# ESFDv1.net
KiCad netlist of a schematic drawn in EAGLE
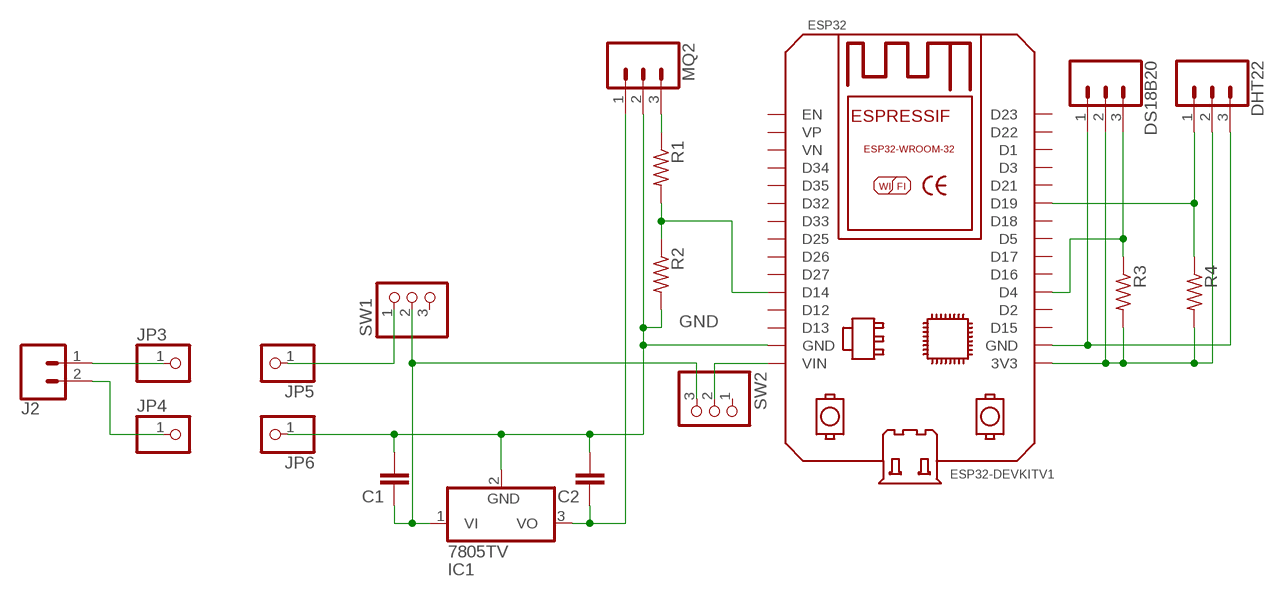
[diagram p0: schematic, sheet 1]

(export (version "E")
  (design (tool "Eeschema 10.0.6"))
  (components
    (comp (ref "C1")
      (value "C5/2.5")
      (footprint "eagle-import:C5B2.5")
      (libsource (lib "eagle-import") (part "C5/2.5"))
    )
    (comp (ref "C2")
      (value "C5/2.5")
      (footprint "eagle-import:C5B2.5")
      (libsource (lib "eagle-import") (part "C5/2.5"))
    )
    (comp (ref "DHT22")
      (value "CONN_03-SCREW-5MM")
      (footprint "eagle-import:SCREWTERMINAL-5MM-3")
      (libsource (lib "eagle-import") (part "CONN_03-SCREW-5MM"))
    )
    (comp (ref "DS18B20")
      (value "CONN_03-SCREW-5MM")
      (footprint "eagle-import:SCREWTERMINAL-5MM-3")
      (libsource (lib "eagle-import") (part "CONN_03-SCREW-5MM"))
    )
    (comp (ref "ESP32")
      (value "ESP32DEVKITV1")
      (footprint "eagle-import:ESP32-DEVKITV1")
      (libsource (lib "eagle-import") (part "ESP32DEVKITV1"))
    )
    (comp (ref "IC1")
      (value "7805TV")
      (footprint "eagle-import:TO220V")
      (libsource (lib "eagle-import") (part "78TV05"))
    )
    (comp (ref "J2")
      (value "CONN_025MM")
      (footprint "eagle-import:SCREWTERMINAL-5MM-2")
      (libsource (lib "eagle-import") (part "CONN_025MM"))
    )
    (comp (ref "JP3")
      (value "PINHD-1X1")
      (footprint "eagle-import:1X01")
      (libsource (lib "eagle-import") (part "PINHD-1X1"))
    )
    (comp (ref "JP4")
      (value "PINHD-1X1")
      (footprint "eagle-import:1X01")
      (libsource (lib "eagle-import") (part "PINHD-1X1"))
    )
    (comp (ref "JP5")
      (value "PINHD-1X1")
      (footprint "eagle-import:1X01")
      (libsource (lib "eagle-import") (part "PINHD-1X1"))
    )
    (comp (ref "JP6")
      (value "PINHD-1X1")
      (footprint "eagle-import:1X01")
      (libsource (lib "eagle-import") (part "PINHD-1X1"))
    )
    (comp (ref "MQ2")
      (value "CONN_03-SCREW-5MM")
      (footprint "eagle-import:SCREWTERMINAL-5MM-3")
      (libsource (lib "eagle-import") (part "CONN_03-SCREW-5MM"))
    )
    (comp (ref "R1")
      (value "R-US_0309/12")
      (footprint "eagle-import:0309_12")
      (libsource (lib "eagle-import") (part "R-US_0309/12"))
    )
    (comp (ref "R2")
      (value "R-US_0309/12")
      (footprint "eagle-import:0309_12")
      (libsource (lib "eagle-import") (part "R-US_0309/12"))
    )
    (comp (ref "R3")
      (value "R-US_0414/15")
      (footprint "eagle-import:0414_15")
      (libsource (lib "eagle-import") (part "R-US_0414/15"))
    )
    (comp (ref "R4")
      (value "R-US_0414/15")
      (footprint "eagle-import:0414_15")
      (libsource (lib "eagle-import") (part "R-US_0414/15"))
    )
    (comp (ref "SW1")
      (value "PINHD-1X3")
      (footprint "eagle-import:1X03")
      (libsource (lib "eagle-import") (part "PINHD-1X3"))
    )
    (comp (ref "SW2")
      (value "PINHD-1X3")
      (footprint "eagle-import:1X03")
      (libsource (lib "eagle-import") (part "PINHD-1X3"))
    )
  )
  (nets
    (net (code "1") (name "/GND") (class "Default")
      (node (ref "C1") (pin "2") (pinfunction "2_2") (pintype "passive"))
      (node (ref "C2") (pin "2") (pinfunction "2_2") (pintype "passive"))
      (node (ref "DHT22") (pin "3") (pinfunction "3_3") (pintype "passive"))
      (node (ref "DS18B20") (pin "1") (pinfunction "1_1") (pintype "passive"))
      (node (ref "ESP32") (pin "GND") (pinfunction "GND_GND") (pintype "bidirectional"))
      (node (ref "ESP32") (pin "GND@1") (pinfunction "GND_GND@1") (pintype "bidirectional"))
      (node (ref "IC1") (pin "2") (pinfunction "GND_2") (pintype "passive"))
      (node (ref "JP6") (pin "1") (pinfunction "1_1") (pintype "passive"))
      (node (ref "MQ2") (pin "2") (pinfunction "2_2") (pintype "passive"))
      (node (ref "R2") (pin "2") (pinfunction "2_2") (pintype "passive"))
    )
    (net (code "2") (name "Net-(DHT22-Pad1)") (class "Default")
      (node (ref "DHT22") (pin "1") (pinfunction "1_1") (pintype "passive"))
      (node (ref "ESP32") (pin "D19") (pinfunction "D19_D19") (pintype "bidirectional"))
      (node (ref "R4") (pin "1") (pinfunction "1_1") (pintype "passive"))
    )
    (net (code "3") (name "Net-(DHT22-Pad2)") (class "Default")
      (node (ref "DHT22") (pin "2") (pinfunction "2_2") (pintype "passive"))
      (node (ref "DS18B20") (pin "2") (pinfunction "2_2") (pintype "passive"))
      (node (ref "ESP32") (pin "3V3") (pinfunction "3V3_3V3") (pintype "bidirectional"))
      (node (ref "R3") (pin "2") (pinfunction "2_2") (pintype "passive"))
      (node (ref "R4") (pin "2") (pinfunction "2_2") (pintype "passive"))
    )
    (net (code "4") (name "Net-(DS18B20-Pad3)") (class "Default")
      (node (ref "DS18B20") (pin "3") (pinfunction "3_3") (pintype "passive"))
      (node (ref "ESP32") (pin "D4") (pinfunction "D4_D4") (pintype "bidirectional"))
      (node (ref "R3") (pin "1") (pinfunction "1_1") (pintype "passive"))
    )
    (net (code "5") (name "Net-(ESP32-PadD14)") (class "Default")
      (node (ref "ESP32") (pin "D14") (pinfunction "D14_D14") (pintype "bidirectional"))
      (node (ref "R1") (pin "2") (pinfunction "2_2") (pintype "passive"))
      (node (ref "R2") (pin "1") (pinfunction "1_1") (pintype "passive"))
    )
    (net (code "6") (name "Net-(ESP32-PadVIN)") (class "Default")
      (node (ref "ESP32") (pin "VIN") (pinfunction "VIN_VIN") (pintype "bidirectional"))
      (node (ref "SW2") (pin "2") (pinfunction "2_2") (pintype "passive"))
    )
    (net (code "7") (name "Net-(IC1-VI)") (class "Default")
      (node (ref "C1") (pin "1") (pinfunction "1_1") (pintype "passive"))
      (node (ref "IC1") (pin "1") (pinfunction "VI_1") (pintype "input"))
      (node (ref "SW1") (pin "2") (pinfunction "2_2") (pintype "passive"))
      (node (ref "SW2") (pin "3") (pinfunction "3_3") (pintype "passive"))
    )
    (net (code "8") (name "Net-(IC1-VO)") (class "Default")
      (node (ref "C2") (pin "1") (pinfunction "1_1") (pintype "passive"))
      (node (ref "IC1") (pin "3") (pinfunction "VO_3") (pintype "passive"))
      (node (ref "MQ2") (pin "1") (pinfunction "1_1") (pintype "passive"))
    )
    (net (code "9") (name "Net-(J2-Pad1)") (class "Default")
      (node (ref "J2") (pin "1") (pinfunction "1_1") (pintype "passive"))
      (node (ref "JP3") (pin "1") (pinfunction "1_1") (pintype "passive"))
    )
    (net (code "10") (name "Net-(J2-Pad2)") (class "Default")
      (node (ref "J2") (pin "2") (pinfunction "2_2") (pintype "passive"))
      (node (ref "JP4") (pin "1") (pinfunction "1_1") (pintype "passive"))
    )
    (net (code "11") (name "Net-(JP5-Pad1)") (class "Default")
      (node (ref "JP5") (pin "1") (pinfunction "1_1") (pintype "passive"))
      (node (ref "SW1") (pin "1") (pinfunction "1_1") (pintype "passive"))
    )
    (net (code "12") (name "Net-(MQ2-Pad3)") (class "Default")
      (node (ref "MQ2") (pin "3") (pinfunction "3_3") (pintype "passive"))
      (node (ref "R1") (pin "1") (pinfunction "1_1") (pintype "passive"))
    )
    (net (code "13") (name "unconnected-(ESP32-PadD1)") (class "Default")
      (node (ref "ESP32") (pin "D1") (pinfunction "D1_D1") (pintype "bidirectional"))
    )
    (net (code "14") (name "unconnected-(ESP32-PadD2)") (class "Default")
      (node (ref "ESP32") (pin "D2") (pinfunction "D2_D2") (pintype "bidirectional"))
    )
    (net (code "15") (name "unconnected-(ESP32-PadD3)") (class "Default")
      (node (ref "ESP32") (pin "D3") (pinfunction "D3_D3") (pintype "bidirectional"))
    )
    (net (code "16") (name "unconnected-(ESP32-PadD5)") (class "Default")
      (node (ref "ESP32") (pin "D5") (pinfunction "D5_D5") (pintype "bidirectional"))
    )
    (net (code "17") (name "unconnected-(ESP32-PadD12)") (class "Default")
      (node (ref "ESP32") (pin "D12") (pinfunction "D12_D12") (pintype "bidirectional"))
    )
    (net (code "18") (name "unconnected-(ESP32-PadD13)") (class "Default")
      (node (ref "ESP32") (pin "D13") (pinfunction "D13_D13") (pintype "bidirectional"))
    )
    (net (code "19") (name "unconnected-(ESP32-PadD15)") (class "Default")
      (node (ref "ESP32") (pin "D15") (pinfunction "D15_D15") (pintype "bidirectional"))
    )
    (net (code "20") (name "unconnected-(ESP32-PadD16)") (class "Default")
      (node (ref "ESP32") (pin "D16") (pinfunction "D16_D16") (pintype "bidirectional"))
    )
    (net (code "21") (name "unconnected-(ESP32-PadD17)") (class "Default")
      (node (ref "ESP32") (pin "D17") (pinfunction "D17_D17") (pintype "bidirectional"))
    )
    (net (code "22") (name "unconnected-(ESP32-PadD18)") (class "Default")
      (node (ref "ESP32") (pin "D18") (pinfunction "D18_D18") (pintype "bidirectional"))
    )
    (net (code "23") (name "unconnected-(ESP32-PadD21)") (class "Default")
      (node (ref "ESP32") (pin "D21") (pinfunction "D21_D21") (pintype "bidirectional"))
    )
    (net (code "24") (name "unconnected-(ESP32-PadD22)") (class "Default")
      (node (ref "ESP32") (pin "D22") (pinfunction "D22_D22") (pintype "bidirectional"))
    )
    (net (code "25") (name "unconnected-(ESP32-PadD23)") (class "Default")
      (node (ref "ESP32") (pin "D23") (pinfunction "D23_D23") (pintype "bidirectional"))
    )
    (net (code "26") (name "unconnected-(ESP32-PadD25)") (class "Default")
      (node (ref "ESP32") (pin "D25") (pinfunction "D25_D25") (pintype "bidirectional"))
    )
    (net (code "27") (name "unconnected-(ESP32-PadD26)") (class "Default")
      (node (ref "ESP32") (pin "D26") (pinfunction "D26_D26") (pintype "bidirectional"))
    )
    (net (code "28") (name "unconnected-(ESP32-PadD27)") (class "Default")
      (node (ref "ESP32") (pin "D27") (pinfunction "D27_D27") (pintype "bidirectional"))
    )
    (net (code "29") (name "unconnected-(ESP32-PadD32)") (class "Default")
      (node (ref "ESP32") (pin "D32") (pinfunction "D32_D32") (pintype "bidirectional"))
    )
    (net (code "30") (name "unconnected-(ESP32-PadD33)") (class "Default")
      (node (ref "ESP32") (pin "D33") (pinfunction "D33_D33") (pintype "bidirectional"))
    )
    (net (code "31") (name "unconnected-(ESP32-PadD34)") (class "Default")
      (node (ref "ESP32") (pin "D34") (pinfunction "D34_D34") (pintype "bidirectional"))
    )
    (net (code "32") (name "unconnected-(ESP32-PadD35)") (class "Default")
      (node (ref "ESP32") (pin "D35") (pinfunction "D35_D35") (pintype "bidirectional"))
    )
    (net (code "33") (name "unconnected-(ESP32-PadEN)") (class "Default")
      (node (ref "ESP32") (pin "EN") (pinfunction "EN_EN") (pintype "bidirectional"))
    )
    (net (code "34") (name "unconnected-(ESP32-PadVN)") (class "Default")
      (node (ref "ESP32") (pin "VN") (pinfunction "VN_VN") (pintype "bidirectional"))
    )
    (net (code "35") (name "unconnected-(ESP32-PadVP)") (class "Default")
      (node (ref "ESP32") (pin "VP") (pinfunction "VP_VP") (pintype "bidirectional"))
    )
    (net (code "36") (name "unconnected-(SW1-Pad3)") (class "Default")
      (node (ref "SW1") (pin "3") (pinfunction "3_3") (pintype "passive"))
    )
    (net (code "37") (name "unconnected-(SW2-Pad1)") (class "Default")
      (node (ref "SW2") (pin "1") (pinfunction "1_1") (pintype "passive"))
    )
  )
)
